# Measurment_ICs.net
KiCad netlist of a schematic drawn in Altium Designer
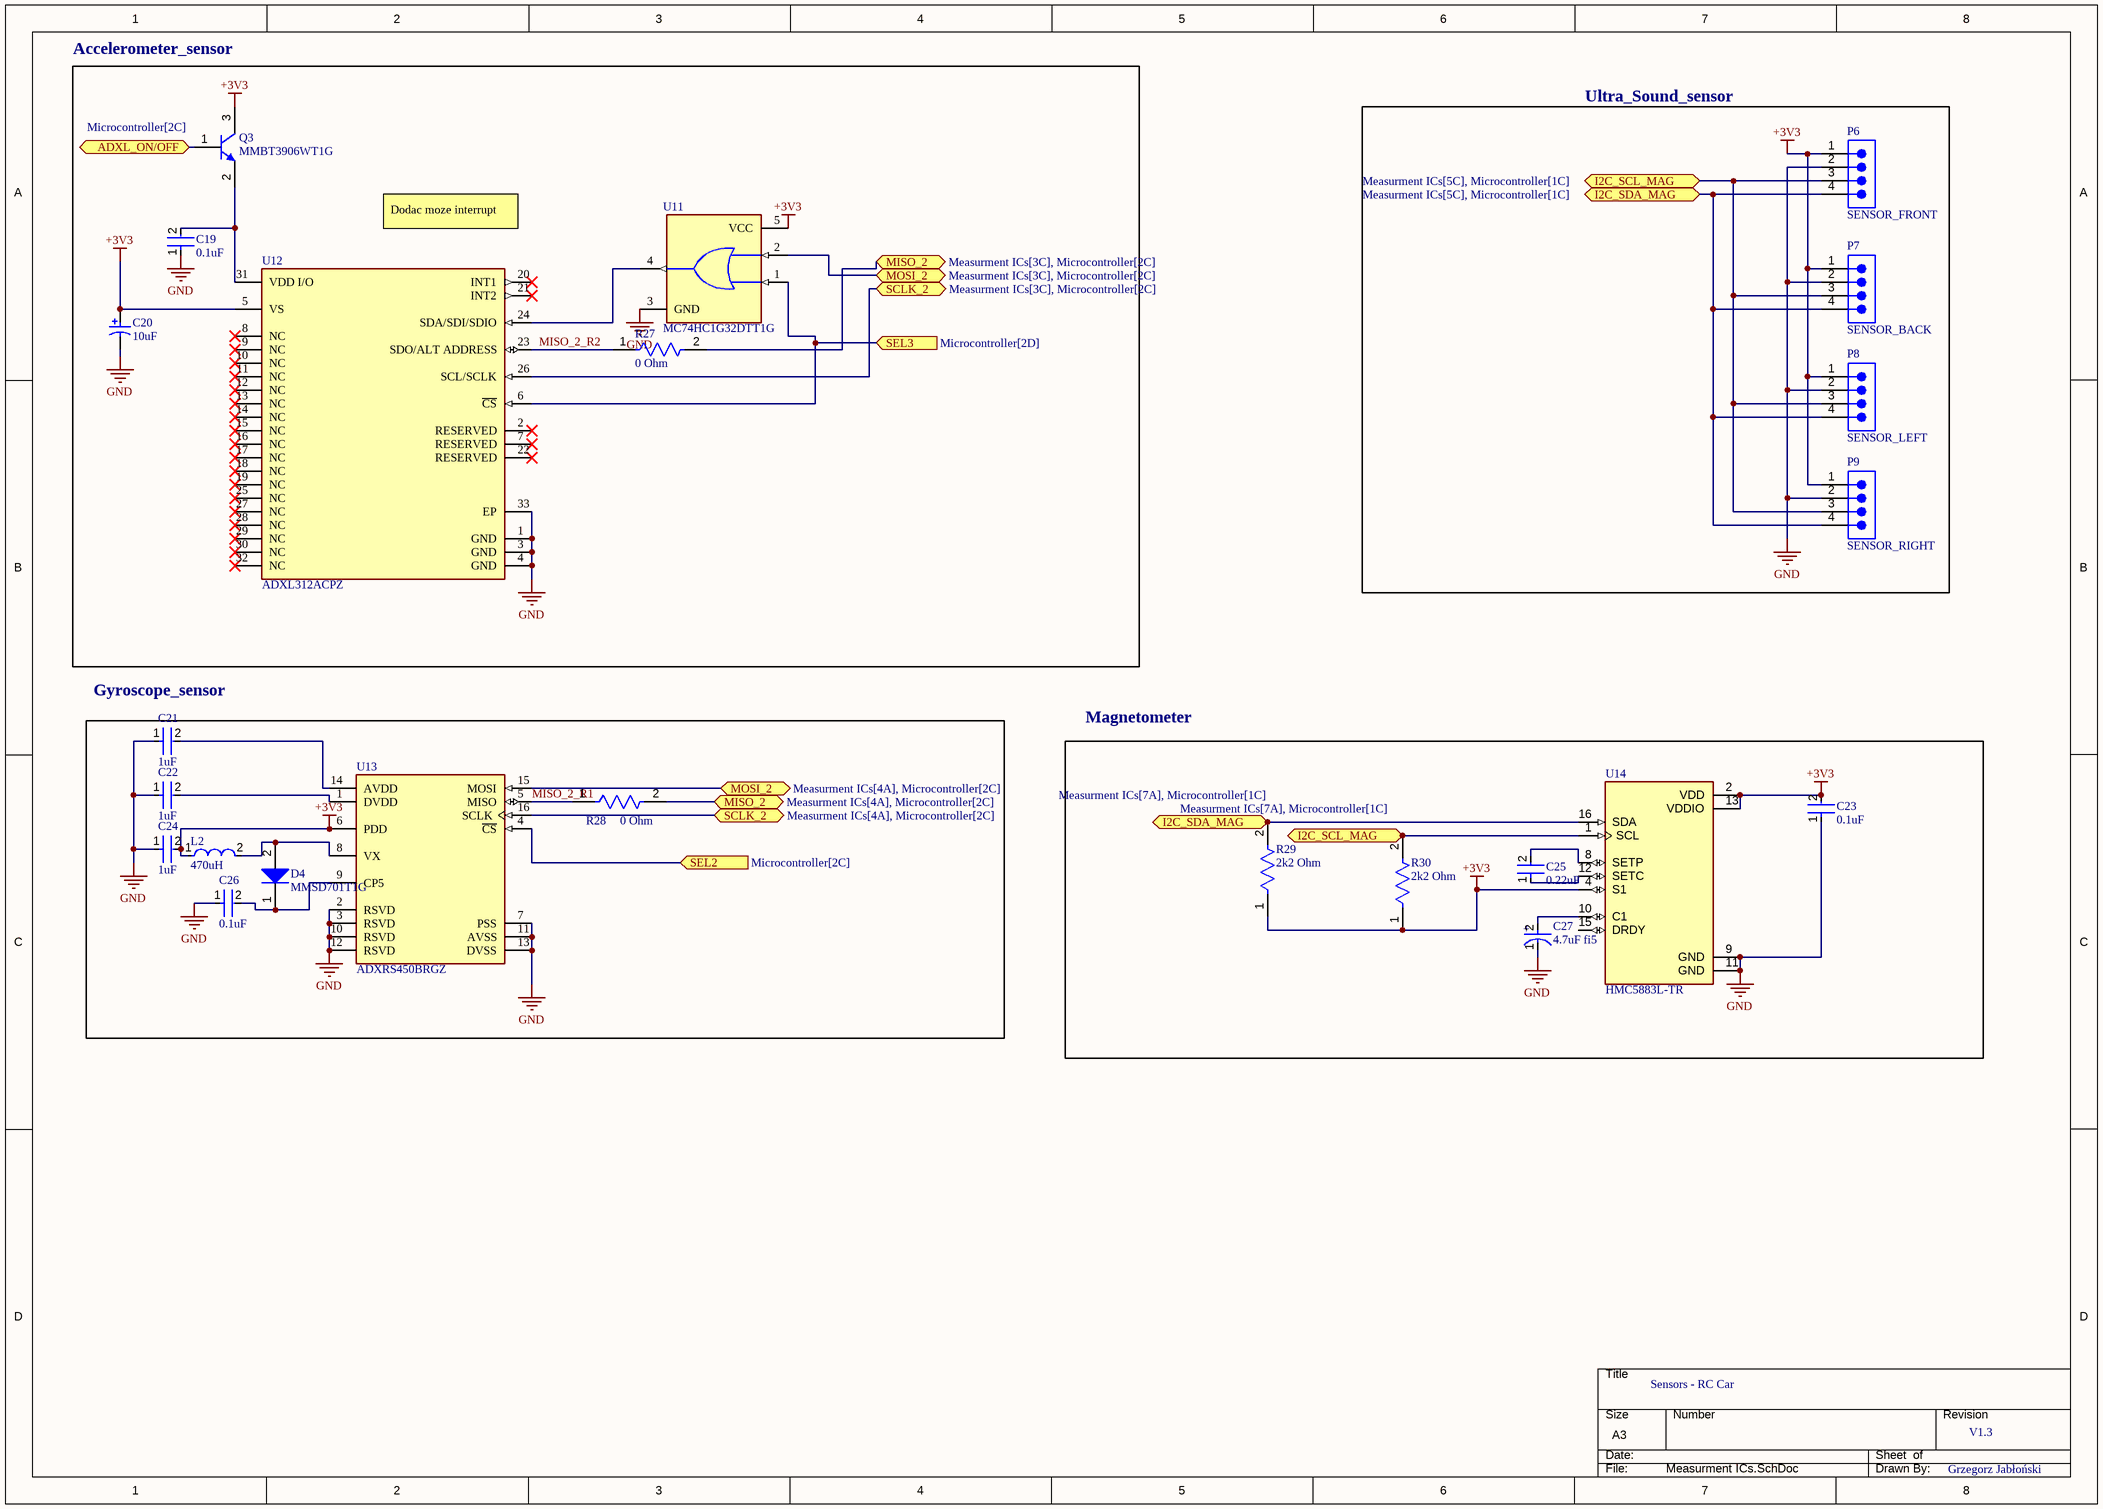
[diagram p0: Measurment ICs.SchDoc]

(export (version "E")
  (design (tool "Eeschema 10.0.6"))
  (components
    (comp (ref "C19")
      (value "0.1uF")
      (footprint "FP-CC0805-0_85-MFG")
      (description "CAP CER 0.1UF 50V X7R 0805")
      (fields (field (name "TOLERANCE") "0.1") (field (name "MANUFACTURER PART NUMBER") "CC0805KRX7R9BB104"))
      (libsource (lib "Altium Content Vault") (part "11868f565c42a9108669ba33697ecf6"))
    )
    (comp (ref "C20")
      (value "10uF")
      (footprint "KEMT-A-3216-18-2_M")
      (description "Capacitor, Tantalum, 10 uF, +/- 10%, 10 V, -55 to 125 degC, 2-Pin SMD (1206), RoHS, Tape and Reel")
      (fields (field (name "TOLERANCE") "±10%") (field (name "MANUFACTURER") "Kemet"))
      (libsource (lib "Altium Content Vault") (part "CAP-P-2"))
    )
    (comp (ref "C21")
      (value "1uF")
      (footprint "FP-CC0805-0_85-MFG")
      (description "CAP CER 0.1UF 50V X7R 0805")
      (fields (field (name "TOLERANCE") "0.1") (field (name "MANUFACTURER PART NUMBER") "CC0805KRX7R9BB104"))
      (libsource (lib "Altium Content Vault") (part "11868f565c42a9108669ba33697ecf6"))
    )
    (comp (ref "C22")
      (value "1uF")
      (footprint "FP-CC0805-0_85-MFG")
      (description "CAP CER 0.1UF 50V X7R 0805")
      (fields (field (name "TOLERANCE") "0.1") (field (name "MANUFACTURER PART NUMBER") "CC0805KRX7R9BB104"))
      (libsource (lib "Altium Content Vault") (part "11868f565c42a9108669ba33697ecf6"))
    )
    (comp (ref "C23")
      (value "0.1uF")
      (footprint "FP-CC0805-0_85-MFG")
      (description "CAP CER 0.1UF 50V X7R 0805")
      (fields (field (name "TOLERANCE") "0.1") (field (name "MANUFACTURER PART NUMBER") "CC0805KRX7R9BB104"))
      (libsource (lib "Altium Content Vault") (part "11868f565c42a9108669ba33697ecf6"))
    )
    (comp (ref "C24")
      (value "1uF")
      (footprint "FP-CC0805-0_85-MFG")
      (description "CAP CER 0.1UF 50V X7R 0805")
      (fields (field (name "TOLERANCE") "0.1") (field (name "MANUFACTURER PART NUMBER") "CC0805KRX7R9BB104"))
      (libsource (lib "Altium Content Vault") (part "11868f565c42a9108669ba33697ecf6"))
    )
    (comp (ref "C25")
      (value "0.22uF")
      (footprint "FP-CC0805-0_85-MFG")
      (description "CAP CER 0.1UF 50V X7R 0805")
      (fields (field (name "TOLERANCE") "0.1") (field (name "MANUFACTURER PART NUMBER") "CC0805KRX7R9BB104"))
      (libsource (lib "Altium Content Vault") (part "11868f565c42a9108669ba33697ecf6"))
    )
    (comp (ref "C26")
      (value "0.1uF")
      (footprint "FP-CC0805-0_85-MFG")
      (description "CAP CER 0.1UF 50V X7R 0805")
      (fields (field (name "TOLERANCE") "0.1") (field (name "MANUFACTURER PART NUMBER") "CC0805KRX7R9BB104"))
      (libsource (lib "Altium Content Vault") (part "11868f565c42a9108669ba33697ecf6"))
    )
    (comp (ref "C27")
      (value "4.7uF fi5")
      (footprint "FP-RAD-TH-D_5_0_5-L_11_1-MFG")
      (description "Aluminum Electrolytic Capacitors (Radial Lead Type) AEC-Q200 Qualified 22uF ±20% 50V")
      (fields (field (name "TOLERANCE") "20%"))
      (libsource (lib "Altium Content Vault") (part "a00bbbee19879c290e62620ae7e47b1"))
    )
    (comp (ref "D4")
      (value "MMSD701T1G")
      (footprint "ONSC-SOD-123-2-425-04_V")
      (description "Schottky Barrier Diode, 2-Pin SOD-123, Pb-Free, Tape and Reel")
      (fields (field (name "MANUFACTURER") "On Semiconductor"))
      (libsource (lib "Altium Content Vault") (part "ONSC-D-K1A2-2"))
    )
    (comp (ref "L2")
      (value "470uH")
      (footprint "FP-LQH43CN_03-MFG")
      (description "Wire Wound Ferrite Inductor for General Circuits 470μH ±10% 11.8Ω 80mA 1812")
      (fields (field (name "TOLERANCE") "10%"))
      (libsource (lib "Altium Content Vault") (part "725321dda6339637d4d059423bc1c3c"))
    )
    (comp (ref "P6")
      (value "SENSOR_FRONT")
      (footprint "61300411121")
      (libsource (lib "Altium Content Vault") (part "Header_Male_1R_04P"))
    )
    (comp (ref "P7")
      (value "SENSOR_BACK")
      (footprint "61300411121")
      (libsource (lib "Altium Content Vault") (part "Header_Male_1R_04P"))
    )
    (comp (ref "P8")
      (value "SENSOR_LEFT")
      (footprint "61300411121")
      (libsource (lib "Altium Content Vault") (part "Header_Male_1R_04P"))
    )
    (comp (ref "P9")
      (value "SENSOR_RIGHT")
      (footprint "61300411121")
      (libsource (lib "Altium Content Vault") (part "Header_Male_1R_04P"))
    )
    (comp (ref "Q3")
      (value "MMBT3906WT1G")
      (footprint "ONSC-SC-70-3-419-04_V")
      (description "General Purpose Transistor, PNP Silicon, 3-Pin SC70, Pb-Free, Tape and Reel")
      (fields (field (name "MANUFACTURER") "On Semiconductor"))
      (libsource (lib "Altium Content Vault") (part "ONSC-NPN-B1E2C3-3"))
    )
    (comp (ref "R27")
      (value "0 Ohm")
      (footprint "FP-RMCF0805-MFG")
      (description "RES 0 OHM JUMPER 1/8W 0805")
      (libsource (lib "Altium Content Vault") (part "1029c3af85768c4190bb7ad29bc67b5"))
    )
    (comp (ref "R28")
      (value "0 Ohm")
      (footprint "FP-RMCF0805-MFG")
      (description "RES 0 OHM JUMPER 1/8W 0805")
      (libsource (lib "Altium Content Vault") (part "1029c3af85768c4190bb7ad29bc67b5"))
    )
    (comp (ref "R29")
      (value "2k2 Ohm")
      (footprint "FP-RMCF0805-MFG")
      (description "RES 0 OHM JUMPER 1/8W 0805")
      (libsource (lib "Altium Content Vault") (part "1029c3af85768c4190bb7ad29bc67b5"))
    )
    (comp (ref "R30")
      (value "2k2 Ohm")
      (footprint "FP-RMCF0805-MFG")
      (description "RES 0 OHM JUMPER 1/8W 0805")
      (libsource (lib "Altium Content Vault") (part "1029c3af85768c4190bb7ad29bc67b5"))
    )
    (comp (ref "U11")
      (value "MC74HC1G32DTT1G")
      (footprint "FP-483-MFG")
      (description "MC74HC1G32DTT1G MC74HC Series 4 V Surface Mount Single 2-Input OR Gate - TSOP-5")
      (libsource (lib "Altium Content Vault") (part "7dc5fb894309747e1da8625ad87dccb"))
    )
    (comp (ref "U12")
      (value "ADXL312ACPZ")
      (footprint "FP-CP-32-17-MFG")
      (description "ACCEL 1.5-12G I2C/SPI 32LFCSP")
      (libsource (lib "Altium Content Vault") (part "7523e9a6801b99f6cbf95d05348c854"))
    )
    (comp (ref "U13")
      (value "ADXRS450BRGZ")
      (footprint "FP-RG-16-1-IPC_C")
      (description "SENS GYRO 300DEG/S DGTL 16SOIC")
      (libsource (lib "Altium Content Vault") (part "bc2adaa03a4e25db86aafbb646e1801"))
    )
    (comp (ref "U14")
      (value "HMC5883L-TR")
      (footprint "XDCR_HMC5883L-TR")
      (fields (field (name "MF") "STMicroelectronics") (field (name "MP") "HMC5883LTR"))
      (libsource (lib "HMC5883L-TR") (part "HMC5883L-TR"))
    )
  )
  (nets
    (net (code "1") (name "+3V3") (class "Default")
      (node (ref "C20") (pin "1") (pinfunction "1_1") (pintype "passive"))
      (node (ref "C23") (pin "2") (pinfunction "2_2") (pintype "passive"))
      (node (ref "C24") (pin "2") (pinfunction "2_2") (pintype "passive"))
      (node (ref "L2") (pin "1") (pinfunction "1_1") (pintype "passive"))
      (node (ref "P6") (pin "1") (pinfunction "1_1") (pintype "passive"))
      (node (ref "P7") (pin "1") (pinfunction "1_1") (pintype "passive"))
      (node (ref "P8") (pin "1") (pinfunction "1_1") (pintype "passive"))
      (node (ref "P9") (pin "1") (pinfunction "1_1") (pintype "passive"))
      (node (ref "Q3") (pin "3") (pinfunction "C_3") (pintype "passive"))
      (node (ref "R29") (pin "1") (pinfunction "1_1") (pintype "passive"))
      (node (ref "R30") (pin "1") (pinfunction "1_1") (pintype "passive"))
      (node (ref "U11") (pin "5") (pinfunction "VCC_5") (pintype "power_in"))
      (node (ref "U12") (pin "5") (pinfunction "VS_5") (pintype "power_in"))
      (node (ref "U13") (pin "6") (pinfunction "PDD_6") (pintype "power_in"))
      (node (ref "U14") (pin "13") (pinfunction "VDDIO_13") (pintype "power_in"))
      (node (ref "U14") (pin "2") (pinfunction "VDD_2") (pintype "power_in"))
      (node (ref "U14") (pin "4") (pinfunction "S1_4") (pintype "bidirectional"))
    )
    (net (code "2") (name "/ADXL_ON{slash}OFF") (class "Default")
      (node (ref "Q3") (pin "1") (pinfunction "B_1") (pintype "passive"))
    )
    (net (code "3") (name "/I2C_SCL_MAG") (class "Default")
      (node (ref "P6") (pin "3") (pinfunction "3_3") (pintype "passive"))
      (node (ref "P7") (pin "3") (pinfunction "3_3") (pintype "passive"))
      (node (ref "P8") (pin "3") (pinfunction "3_3") (pintype "passive"))
      (node (ref "P9") (pin "3") (pinfunction "3_3") (pintype "passive"))
      (node (ref "R30") (pin "2") (pinfunction "2_2") (pintype "passive"))
      (node (ref "U14") (pin "1") (pinfunction "SCL_1") (pintype "input"))
    )
    (net (code "4") (name "/I2C_SDA_MAG") (class "Default")
      (node (ref "P6") (pin "4") (pinfunction "4_4") (pintype "passive"))
      (node (ref "P7") (pin "4") (pinfunction "4_4") (pintype "passive"))
      (node (ref "P8") (pin "4") (pinfunction "4_4") (pintype "passive"))
      (node (ref "P9") (pin "4") (pinfunction "4_4") (pintype "passive"))
      (node (ref "R29") (pin "2") (pinfunction "2_2") (pintype "passive"))
      (node (ref "U14") (pin "16") (pinfunction "SDA_16") (pintype "input"))
    )
    (net (code "5") (name "/MISO_2") (class "Default")
      (node (ref "R27") (pin "2") (pinfunction "2_2") (pintype "passive"))
      (node (ref "R28") (pin "2") (pinfunction "2_2") (pintype "passive"))
    )
    (net (code "6") (name "/MISO_2_R1") (class "Default")
      (node (ref "R28") (pin "1") (pinfunction "1_1") (pintype "passive"))
      (node (ref "U13") (pin "5") (pinfunction "MISO_5") (pintype "bidirectional"))
    )
    (net (code "7") (name "/MISO_2_R2") (class "Default")
      (node (ref "R27") (pin "1") (pinfunction "1_1") (pintype "passive"))
      (node (ref "U12") (pin "23") (pinfunction "SDO/ALT_ADDRESS_23") (pintype "bidirectional"))
    )
    (net (code "8") (name "/MOSI_2") (class "Default")
      (node (ref "U11") (pin "2") (pinfunction "A_2") (pintype "input"))
      (node (ref "U13") (pin "15") (pinfunction "MOSI_15") (pintype "input"))
    )
    (net (code "9") (name "/SCLK_2") (class "Default")
      (node (ref "U12") (pin "26") (pinfunction "SCL/SCLK_26") (pintype "input"))
      (node (ref "U13") (pin "16") (pinfunction "SCLK_16") (pintype "input"))
    )
    (net (code "10") (name "/SEL2") (class "Default")
      (node (ref "U13") (pin "4") (pinfunction "~{CS}_4") (pintype "input"))
    )
    (net (code "11") (name "/SEL3") (class "Default")
      (node (ref "U11") (pin "1") (pinfunction "B_1") (pintype "input"))
      (node (ref "U12") (pin "6") (pinfunction "~{CS}_6") (pintype "input"))
    )
    (net (code "12") (name "GND") (class "Default")
      (node (ref "C19") (pin "1") (pinfunction "1_1") (pintype "passive"))
      (node (ref "C20") (pin "2") (pinfunction "2_2") (pintype "passive"))
      (node (ref "C21") (pin "1") (pinfunction "1_1") (pintype "passive"))
      (node (ref "C22") (pin "1") (pinfunction "1_1") (pintype "passive"))
      (node (ref "C23") (pin "1") (pinfunction "1_1") (pintype "passive"))
      (node (ref "C24") (pin "1") (pinfunction "1_1") (pintype "passive"))
      (node (ref "C26") (pin "1") (pinfunction "1_1") (pintype "passive"))
      (node (ref "C27") (pin "1") (pinfunction "C_1") (pintype "passive"))
      (node (ref "P6") (pin "2") (pinfunction "2_2") (pintype "passive"))
      (node (ref "P7") (pin "2") (pinfunction "2_2") (pintype "passive"))
      (node (ref "P8") (pin "2") (pinfunction "2_2") (pintype "passive"))
      (node (ref "P9") (pin "2") (pinfunction "2_2") (pintype "passive"))
      (node (ref "U11") (pin "3") (pinfunction "GND_3") (pintype "power_in"))
      (node (ref "U12") (pin "1") (pinfunction "GND_1") (pintype "power_in"))
      (node (ref "U12") (pin "3") (pinfunction "GND_3") (pintype "power_in"))
      (node (ref "U12") (pin "33") (pinfunction "EP_33") (pintype "power_in"))
      (node (ref "U12") (pin "4") (pinfunction "GND_4") (pintype "power_in"))
      (node (ref "U13") (pin "10") (pinfunction "RSVD_10") (pintype "power_in"))
      (node (ref "U13") (pin "11") (pinfunction "AVSS_11") (pintype "power_in"))
      (node (ref "U13") (pin "12") (pinfunction "RSVD_12") (pintype "power_in"))
      (node (ref "U13") (pin "13") (pinfunction "DVSS_13") (pintype "power_in"))
      (node (ref "U13") (pin "2") (pinfunction "RSVD_2") (pintype "power_in"))
      (node (ref "U13") (pin "3") (pinfunction "RSVD_3") (pintype "power_in"))
      (node (ref "U13") (pin "7") (pinfunction "PSS_7") (pintype "power_in"))
      (node (ref "U14") (pin "11") (pinfunction "GND_11") (pintype "power_in"))
      (node (ref "U14") (pin "9") (pinfunction "GND_9") (pintype "power_in"))
    )
    (net (code "13") (name "Net-(C27-A)") (class "Default")
      (node (ref "C27") (pin "2") (pinfunction "A_2") (pintype "passive"))
      (node (ref "U14") (pin "10") (pinfunction "C1_10") (pintype "bidirectional"))
    )
    (net (code "14") (name "Net-(D4-A)") (class "Default")
      (node (ref "D4") (pin "2") (pinfunction "A_2") (pintype "passive"))
      (node (ref "L2") (pin "2") (pinfunction "2_2") (pintype "passive"))
      (node (ref "U13") (pin "8") (pinfunction "VX_8") (pintype "power_in"))
    )
    (net (code "15") (name "Net-(D4-K)") (class "Default")
      (node (ref "C26") (pin "2") (pinfunction "2_2") (pintype "passive"))
      (node (ref "D4") (pin "1") (pinfunction "K_1") (pintype "passive"))
      (node (ref "U13") (pin "9") (pinfunction "CP5_9") (pintype "power_in"))
    )
    (net (code "16") (name "Net-(Q3-E)") (class "Default")
      (node (ref "C19") (pin "2") (pinfunction "2_2") (pintype "passive"))
      (node (ref "Q3") (pin "2") (pinfunction "E_2") (pintype "passive"))
      (node (ref "U12") (pin "31") (pinfunction "VDD_I/O_31") (pintype "power_in"))
    )
    (net (code "17") (name "Net-(U11-Y)") (class "Default")
      (node (ref "U11") (pin "4") (pinfunction "Y_4") (pintype "output"))
      (node (ref "U12") (pin "24") (pinfunction "SDA/SDI/SDIO_24") (pintype "input"))
    )
    (net (code "18") (name "Net-(U13-AVDD)") (class "Default")
      (node (ref "C21") (pin "2") (pinfunction "2_2") (pintype "passive"))
      (node (ref "U13") (pin "14") (pinfunction "AVDD_14") (pintype "power_in"))
    )
    (net (code "19") (name "Net-(U13-DVDD)") (class "Default")
      (node (ref "C22") (pin "2") (pinfunction "2_2") (pintype "passive"))
      (node (ref "U13") (pin "1") (pinfunction "DVDD_1") (pintype "power_in"))
    )
    (net (code "20") (name "Net-(U14-SETC)") (class "Default")
      (node (ref "C25") (pin "1") (pinfunction "1_1") (pintype "passive"))
      (node (ref "U14") (pin "12") (pinfunction "SETC_12") (pintype "bidirectional"))
    )
    (net (code "21") (name "Net-(U14-SETP)") (class "Default")
      (node (ref "C25") (pin "2") (pinfunction "2_2") (pintype "passive"))
      (node (ref "U14") (pin "8") (pinfunction "SETP_8") (pintype "bidirectional"))
    )
    (net (code "22") (name "unconnected-(U12-INT1-Pad20)") (class "Default")
      (node (ref "U12") (pin "20") (pinfunction "INT1_20") (pintype "output+no_connect"))
    )
    (net (code "23") (name "unconnected-(U12-INT2-Pad21)") (class "Default")
      (node (ref "U12") (pin "21") (pinfunction "INT2_21") (pintype "output+no_connect"))
    )
    (net (code "24") (name "unconnected-(U12-NC-Pad8)") (class "Default")
      (node (ref "U12") (pin "8") (pinfunction "NC_8") (pintype "passive+no_connect"))
    )
    (net (code "25") (name "unconnected-(U12-NC-Pad9)") (class "Default")
      (node (ref "U12") (pin "9") (pinfunction "NC_9") (pintype "passive+no_connect"))
    )
    (net (code "26") (name "unconnected-(U12-NC-Pad10)") (class "Default")
      (node (ref "U12") (pin "10") (pinfunction "NC_10") (pintype "passive+no_connect"))
    )
    (net (code "27") (name "unconnected-(U12-NC-Pad11)") (class "Default")
      (node (ref "U12") (pin "11") (pinfunction "NC_11") (pintype "passive+no_connect"))
    )
    (net (code "28") (name "unconnected-(U12-NC-Pad12)") (class "Default")
      (node (ref "U12") (pin "12") (pinfunction "NC_12") (pintype "passive+no_connect"))
    )
    (net (code "29") (name "unconnected-(U12-NC-Pad13)") (class "Default")
      (node (ref "U12") (pin "13") (pinfunction "NC_13") (pintype "passive+no_connect"))
    )
    (net (code "30") (name "unconnected-(U12-NC-Pad14)") (class "Default")
      (node (ref "U12") (pin "14") (pinfunction "NC_14") (pintype "passive+no_connect"))
    )
    (net (code "31") (name "unconnected-(U12-NC-Pad15)") (class "Default")
      (node (ref "U12") (pin "15") (pinfunction "NC_15") (pintype "passive+no_connect"))
    )
    (net (code "32") (name "unconnected-(U12-NC-Pad16)") (class "Default")
      (node (ref "U12") (pin "16") (pinfunction "NC_16") (pintype "passive+no_connect"))
    )
    (net (code "33") (name "unconnected-(U12-NC-Pad17)") (class "Default")
      (node (ref "U12") (pin "17") (pinfunction "NC_17") (pintype "passive+no_connect"))
    )
    (net (code "34") (name "unconnected-(U12-NC-Pad18)") (class "Default")
      (node (ref "U12") (pin "18") (pinfunction "NC_18") (pintype "passive+no_connect"))
    )
    (net (code "35") (name "unconnected-(U12-NC-Pad19)") (class "Default")
      (node (ref "U12") (pin "19") (pinfunction "NC_19") (pintype "passive+no_connect"))
    )
    (net (code "36") (name "unconnected-(U12-NC-Pad25)") (class "Default")
      (node (ref "U12") (pin "25") (pinfunction "NC_25") (pintype "passive+no_connect"))
    )
    (net (code "37") (name "unconnected-(U12-NC-Pad27)") (class "Default")
      (node (ref "U12") (pin "27") (pinfunction "NC_27") (pintype "passive+no_connect"))
    )
    (net (code "38") (name "unconnected-(U12-NC-Pad28)") (class "Default")
      (node (ref "U12") (pin "28") (pinfunction "NC_28") (pintype "passive+no_connect"))
    )
    (net (code "39") (name "unconnected-(U12-NC-Pad29)") (class "Default")
      (node (ref "U12") (pin "29") (pinfunction "NC_29") (pintype "passive+no_connect"))
    )
    (net (code "40") (name "unconnected-(U12-NC-Pad30)") (class "Default")
      (node (ref "U12") (pin "30") (pinfunction "NC_30") (pintype "passive+no_connect"))
    )
    (net (code "41") (name "unconnected-(U12-NC-Pad32)") (class "Default")
      (node (ref "U12") (pin "32") (pinfunction "NC_32") (pintype "passive+no_connect"))
    )
    (net (code "42") (name "unconnected-(U12-RESERVED-Pad2)") (class "Default")
      (node (ref "U12") (pin "2") (pinfunction "RESERVED_2") (pintype "passive+no_connect"))
    )
    (net (code "43") (name "unconnected-(U12-RESERVED-Pad7)") (class "Default")
      (node (ref "U12") (pin "7") (pinfunction "RESERVED_7") (pintype "passive+no_connect"))
    )
    (net (code "44") (name "unconnected-(U12-RESERVED-Pad22)") (class "Default")
      (node (ref "U12") (pin "22") (pinfunction "RESERVED_22") (pintype "passive+no_connect"))
    )
    (net (code "45") (name "unconnected-(U14-DRDY-Pad15)") (class "Default")
      (node (ref "U14") (pin "15") (pinfunction "DRDY_15") (pintype "bidirectional"))
    )
  )
)
